# countdown4digit.net
KiCad netlist of a schematic drawn in EAGLE
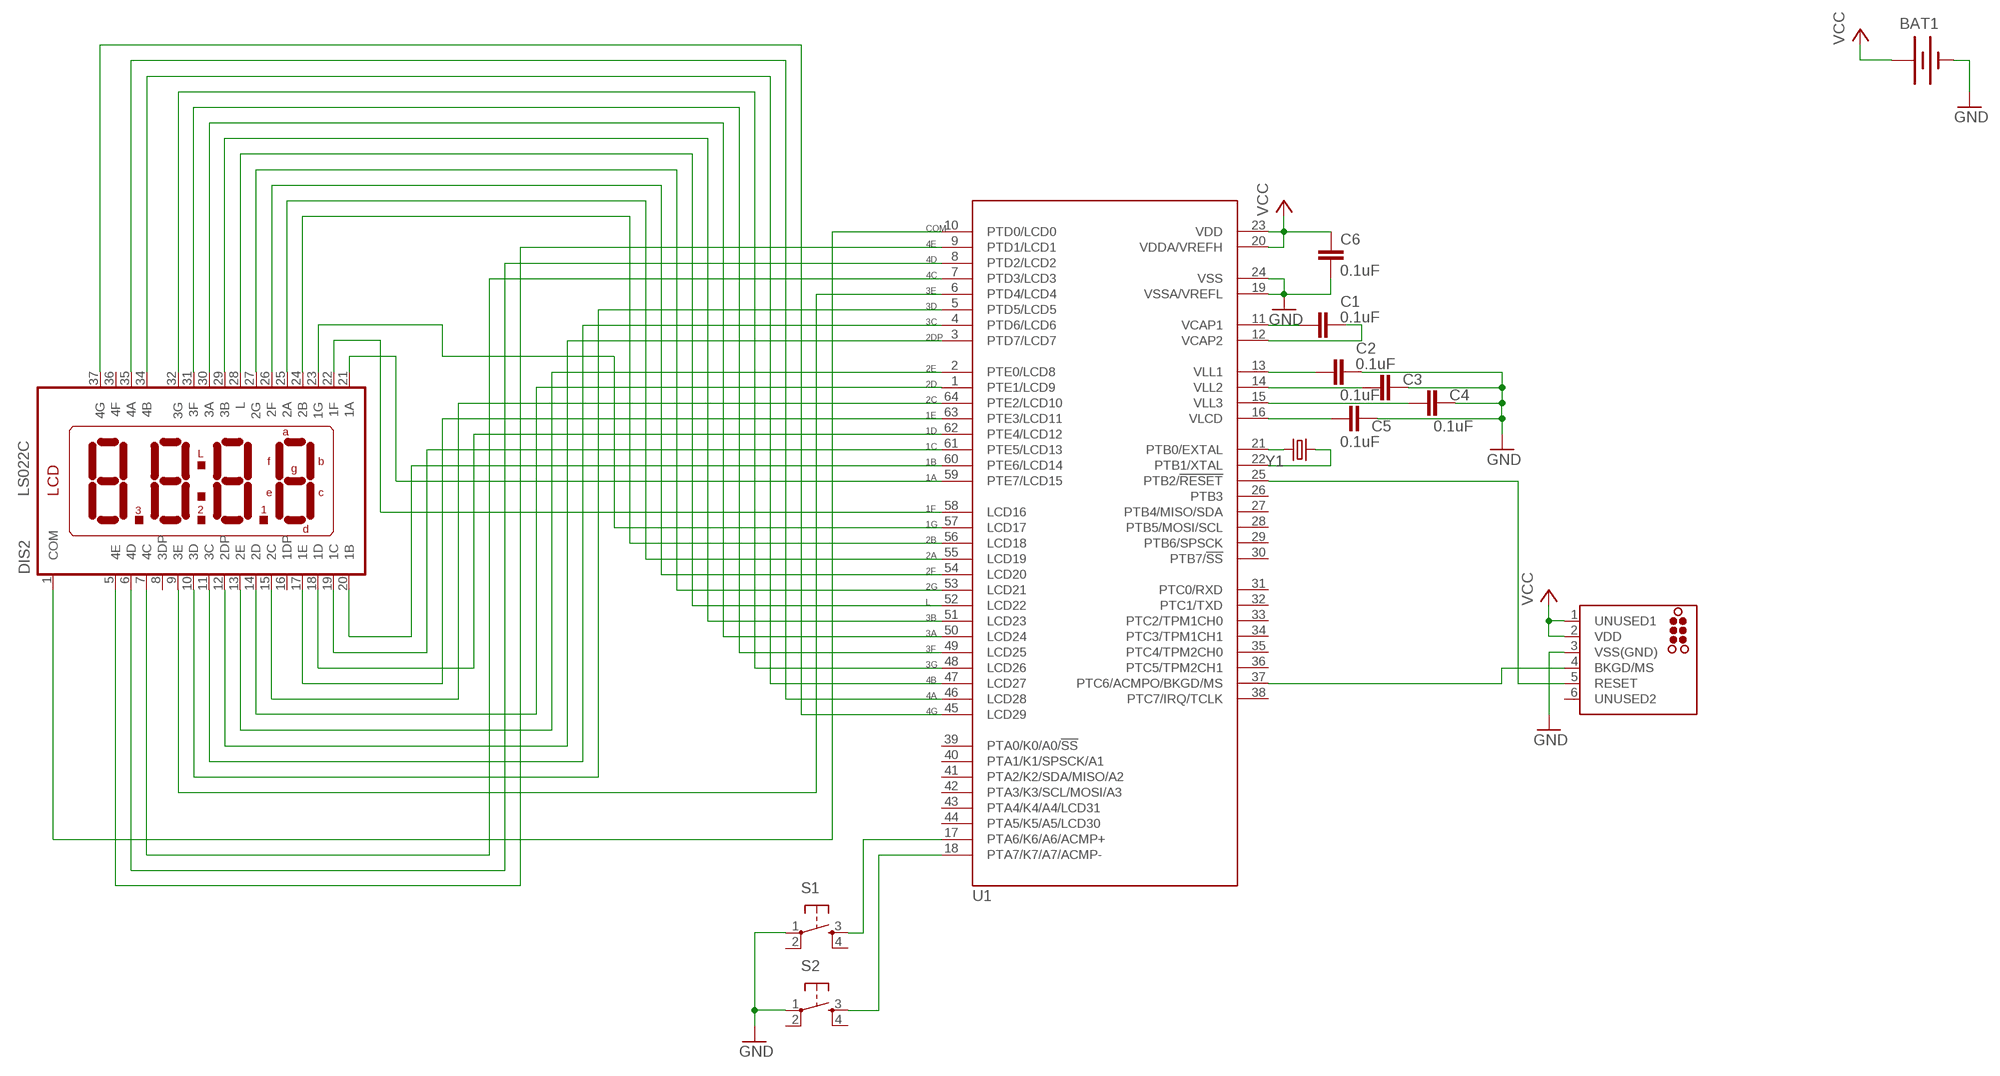
[diagram p0: schematic, sheet 1]

(export (version "E")
  (design (tool "Eeschema 10.0.6"))
  (components
    (comp (ref "BAT1")
      (value "BATTERY12MM")
      (footprint "eagle-import:BATTCON_12MM")
      (libsource (lib "eagle-import") (part "BATTERY12MM"))
    )
    (comp (ref "BDM")
      (value "TC2030-MCP-NL")
      (footprint "eagle-import:TC2030-MCP-NL")
      (libsource (lib "eagle-import") (part "TC2030-MCP-NL"))
    )
    (comp (ref "C1")
      (value "0.1uF")
      (footprint "eagle-import:C0603K")
      (libsource (lib "eagle-import") (part "C-EUC0603K"))
    )
    (comp (ref "C2")
      (value "0.1uF")
      (footprint "eagle-import:C0603K")
      (libsource (lib "eagle-import") (part "C-EUC0603K"))
    )
    (comp (ref "C3")
      (value "0.1uF")
      (footprint "eagle-import:C0603K")
      (libsource (lib "eagle-import") (part "C-EUC0603K"))
    )
    (comp (ref "C4")
      (value "0.1uF")
      (footprint "eagle-import:C0603K")
      (libsource (lib "eagle-import") (part "C-EUC0603K"))
    )
    (comp (ref "C5")
      (value "0.1uF")
      (footprint "eagle-import:C0603K")
      (libsource (lib "eagle-import") (part "C-EUC0603K"))
    )
    (comp (ref "C6")
      (value "0.1uF")
      (footprint "eagle-import:C0603K")
      (libsource (lib "eagle-import") (part "C-EUC0603K"))
    )
    (comp (ref "DIS2")
      (value "LS022C")
      (footprint "eagle-import:LS022C")
      (libsource (lib "eagle-import") (part "LS022C"))
    )
    (comp (ref "S1")
      (value "TAC_SWITCHSMD")
      (footprint "eagle-import:TACTILE_SWITCH_SMD")
      (libsource (lib "eagle-import") (part "TAC_SWITCHSMD"))
    )
    (comp (ref "S2")
      (value "TAC_SWITCHSMD")
      (footprint "eagle-import:TACTILE_SWITCH_SMD")
      (libsource (lib "eagle-import") (part "TAC_SWITCHSMD"))
    )
    (comp (ref "U1")
      (value "MC9S08LL16")
      (footprint "eagle-import:LQFP64")
      (libsource (lib "eagle-import") (part "MC9S08LL16"))
    )
    (comp (ref "Y1")
      (value "CRYSTALTC26H")
      (footprint "eagle-import:TC26H")
      (libsource (lib "eagle-import") (part "CRYSTALTC26H"))
    )
  )
  (nets
    (net (code "1") (name "/1A") (class "Default")
      (node (ref "DIS2") (pin "21") (pinfunction "1A_21") (pintype "passive"))
      (node (ref "U1") (pin "59") (pinfunction "PTE7/LCD15_59") (pintype "bidirectional"))
    )
    (net (code "2") (name "/1B") (class "Default")
      (node (ref "DIS2") (pin "20") (pinfunction "1B_20") (pintype "passive"))
      (node (ref "U1") (pin "60") (pinfunction "PTE6/LCD14_60") (pintype "bidirectional"))
    )
    (net (code "3") (name "/1C") (class "Default")
      (node (ref "DIS2") (pin "19") (pinfunction "1C_19") (pintype "passive"))
      (node (ref "U1") (pin "61") (pinfunction "PTE5/LCD13_61") (pintype "bidirectional"))
    )
    (net (code "4") (name "/1D") (class "Default")
      (node (ref "DIS2") (pin "18") (pinfunction "1D_18") (pintype "passive"))
      (node (ref "U1") (pin "62") (pinfunction "PTE4/LCD12_62") (pintype "bidirectional"))
    )
    (net (code "5") (name "/1E") (class "Default")
      (node (ref "DIS2") (pin "17") (pinfunction "1E_17") (pintype "passive"))
      (node (ref "U1") (pin "63") (pinfunction "PTE3/LCD11_63") (pintype "bidirectional"))
    )
    (net (code "6") (name "/1F") (class "Default")
      (node (ref "DIS2") (pin "22") (pinfunction "1F_22") (pintype "passive"))
      (node (ref "U1") (pin "58") (pinfunction "LCD16_58") (pintype "bidirectional"))
    )
    (net (code "7") (name "/1G") (class "Default")
      (node (ref "DIS2") (pin "23") (pinfunction "1G_23") (pintype "passive"))
      (node (ref "U1") (pin "57") (pinfunction "LCD17_57") (pintype "bidirectional"))
    )
    (net (code "8") (name "/2A") (class "Default")
      (node (ref "DIS2") (pin "25") (pinfunction "2A_25") (pintype "passive"))
      (node (ref "U1") (pin "55") (pinfunction "LCD19_55") (pintype "bidirectional"))
    )
    (net (code "9") (name "/2B") (class "Default")
      (node (ref "DIS2") (pin "24") (pinfunction "2B_24") (pintype "passive"))
      (node (ref "U1") (pin "56") (pinfunction "LCD18_56") (pintype "bidirectional"))
    )
    (net (code "10") (name "/2C") (class "Default")
      (node (ref "DIS2") (pin "15") (pinfunction "2C_15") (pintype "passive"))
      (node (ref "U1") (pin "64") (pinfunction "PTE2/LCD10_64") (pintype "bidirectional"))
    )
    (net (code "11") (name "/2D") (class "Default")
      (node (ref "DIS2") (pin "14") (pinfunction "2D_14") (pintype "passive"))
      (node (ref "U1") (pin "1") (pinfunction "PTE1/LCD9_1") (pintype "bidirectional"))
    )
    (net (code "12") (name "/2DP") (class "Default")
      (node (ref "DIS2") (pin "12") (pinfunction "2DP_12") (pintype "passive"))
      (node (ref "U1") (pin "3") (pinfunction "PTD7/LCD7_3") (pintype "bidirectional"))
    )
    (net (code "13") (name "/2E") (class "Default")
      (node (ref "DIS2") (pin "13") (pinfunction "2E_13") (pintype "passive"))
      (node (ref "U1") (pin "2") (pinfunction "PTE0/LCD8_2") (pintype "bidirectional"))
    )
    (net (code "14") (name "/2F") (class "Default")
      (node (ref "DIS2") (pin "26") (pinfunction "2F_26") (pintype "passive"))
      (node (ref "U1") (pin "54") (pinfunction "LCD20_54") (pintype "bidirectional"))
    )
    (net (code "15") (name "/2G") (class "Default")
      (node (ref "DIS2") (pin "27") (pinfunction "2G_27") (pintype "passive"))
      (node (ref "U1") (pin "53") (pinfunction "LCD21_53") (pintype "bidirectional"))
    )
    (net (code "16") (name "/3A") (class "Default")
      (node (ref "DIS2") (pin "30") (pinfunction "3A_30") (pintype "passive"))
      (node (ref "U1") (pin "50") (pinfunction "LCD24_50") (pintype "bidirectional"))
    )
    (net (code "17") (name "/3B") (class "Default")
      (node (ref "DIS2") (pin "29") (pinfunction "3B_29") (pintype "passive"))
      (node (ref "U1") (pin "51") (pinfunction "LCD23_51") (pintype "bidirectional"))
    )
    (net (code "18") (name "/3C") (class "Default")
      (node (ref "DIS2") (pin "11") (pinfunction "3C_11") (pintype "passive"))
      (node (ref "U1") (pin "4") (pinfunction "PTD6/LCD6_4") (pintype "bidirectional"))
    )
    (net (code "19") (name "/3D") (class "Default")
      (node (ref "DIS2") (pin "10") (pinfunction "3D_10") (pintype "passive"))
      (node (ref "U1") (pin "5") (pinfunction "PTD5/LCD5_5") (pintype "bidirectional"))
    )
    (net (code "20") (name "/3E") (class "Default")
      (node (ref "DIS2") (pin "9") (pinfunction "3E_9") (pintype "passive"))
      (node (ref "U1") (pin "6") (pinfunction "PTD4/LCD4_6") (pintype "bidirectional"))
    )
    (net (code "21") (name "/3F") (class "Default")
      (node (ref "DIS2") (pin "31") (pinfunction "3F_31") (pintype "passive"))
      (node (ref "U1") (pin "49") (pinfunction "LCD25_49") (pintype "bidirectional"))
    )
    (net (code "22") (name "/3G") (class "Default")
      (node (ref "DIS2") (pin "32") (pinfunction "3G_32") (pintype "passive"))
      (node (ref "U1") (pin "48") (pinfunction "LCD26_48") (pintype "bidirectional"))
    )
    (net (code "23") (name "/4A") (class "Default")
      (node (ref "DIS2") (pin "35") (pinfunction "4A_35") (pintype "passive"))
      (node (ref "U1") (pin "46") (pinfunction "LCD28_46") (pintype "bidirectional"))
    )
    (net (code "24") (name "/4B") (class "Default")
      (node (ref "DIS2") (pin "34") (pinfunction "4B_34") (pintype "passive"))
      (node (ref "U1") (pin "47") (pinfunction "LCD27_47") (pintype "bidirectional"))
    )
    (net (code "25") (name "/4C") (class "Default")
      (node (ref "DIS2") (pin "7") (pinfunction "4C_7") (pintype "passive"))
      (node (ref "U1") (pin "7") (pinfunction "PTD3/LCD3_7") (pintype "bidirectional"))
    )
    (net (code "26") (name "/4D") (class "Default")
      (node (ref "DIS2") (pin "6") (pinfunction "4D_6") (pintype "passive"))
      (node (ref "U1") (pin "8") (pinfunction "PTD2/LCD2_8") (pintype "bidirectional"))
    )
    (net (code "27") (name "/4E") (class "Default")
      (node (ref "DIS2") (pin "5") (pinfunction "4E_5") (pintype "passive"))
      (node (ref "U1") (pin "9") (pinfunction "PTD1/LCD1_9") (pintype "bidirectional"))
    )
    (net (code "28") (name "/4G") (class "Default")
      (node (ref "DIS2") (pin "37") (pinfunction "4G_37") (pintype "passive"))
      (node (ref "U1") (pin "45") (pinfunction "LCD29_45") (pintype "bidirectional"))
    )
    (net (code "29") (name "/COM") (class "Default")
      (node (ref "DIS2") (pin "1") (pinfunction "COM_1") (pintype "passive"))
      (node (ref "U1") (pin "10") (pinfunction "PTD0/LCD0_10") (pintype "bidirectional"))
    )
    (net (code "30") (name "/L") (class "Default")
      (node (ref "DIS2") (pin "28") (pinfunction "L_28") (pintype "passive"))
      (node (ref "U1") (pin "52") (pinfunction "LCD22_52") (pintype "bidirectional"))
    )
    (net (code "31") (name "GND") (class "Default")
      (node (ref "BAT1") (pin "GND") (pinfunction "-_GND") (pintype "power_in"))
      (node (ref "BDM") (pin "3") (pinfunction "VSS(GND)_3") (pintype "power_in"))
      (node (ref "C2") (pin "1") (pinfunction "1_1") (pintype "passive"))
      (node (ref "C3") (pin "1") (pinfunction "1_1") (pintype "passive"))
      (node (ref "C4") (pin "1") (pinfunction "1_1") (pintype "passive"))
      (node (ref "C5") (pin "1") (pinfunction "1_1") (pintype "passive"))
      (node (ref "C6") (pin "2") (pinfunction "2_2") (pintype "passive"))
      (node (ref "S1") (pin "1") (pinfunction "1_1") (pintype "passive"))
      (node (ref "S2") (pin "1") (pinfunction "1_1") (pintype "passive"))
      (node (ref "U1") (pin "19") (pinfunction "VSSA/VREFL_19") (pintype "bidirectional"))
      (node (ref "U1") (pin "24") (pinfunction "VSS_24") (pintype "bidirectional"))
    )
    (net (code "32") (name "Net-(BDM-BKGD{slash}MS)") (class "Default")
      (node (ref "BDM") (pin "4") (pinfunction "BKGD/MS_4") (pintype "bidirectional"))
      (node (ref "U1") (pin "37") (pinfunction "PTC6/ACMPO/BKGD/MS_37") (pintype "bidirectional"))
    )
    (net (code "33") (name "Net-(BDM-RESET)") (class "Default")
      (node (ref "BDM") (pin "5") (pinfunction "RESET_5") (pintype "output"))
      (node (ref "U1") (pin "25") (pinfunction "PTB2/~{RESET}_25") (pintype "bidirectional"))
    )
    (net (code "34") (name "Net-(U1-PTA6{slash}K6{slash}A6{slash}ACMP+)") (class "Default")
      (node (ref "S1") (pin "3") (pinfunction "3_3") (pintype "passive"))
      (node (ref "U1") (pin "17") (pinfunction "PTA6/K6/A6/ACMP+_17") (pintype "bidirectional"))
    )
    (net (code "35") (name "Net-(U1-PTA7{slash}K7{slash}A7{slash}ACMP-)") (class "Default")
      (node (ref "S2") (pin "3") (pinfunction "3_3") (pintype "passive"))
      (node (ref "U1") (pin "18") (pinfunction "PTA7/K7/A7/ACMP-_18") (pintype "bidirectional"))
    )
    (net (code "36") (name "Net-(U1-PTB0{slash}EXTAL)") (class "Default")
      (node (ref "U1") (pin "21") (pinfunction "PTB0/EXTAL_21") (pintype "bidirectional"))
      (node (ref "Y1") (pin "2") (pinfunction "2_2") (pintype "passive"))
    )
    (net (code "37") (name "Net-(U1-PTB1{slash}XTAL)") (class "Default")
      (node (ref "U1") (pin "22") (pinfunction "PTB1/XTAL_22") (pintype "bidirectional"))
      (node (ref "Y1") (pin "1") (pinfunction "1_1") (pintype "passive"))
    )
    (net (code "38") (name "Net-(U1-VCAP1)") (class "Default")
      (node (ref "C1") (pin "2") (pinfunction "2_2") (pintype "passive"))
      (node (ref "U1") (pin "11") (pinfunction "VCAP1_11") (pintype "bidirectional"))
    )
    (net (code "39") (name "Net-(U1-VCAP2)") (class "Default")
      (node (ref "C1") (pin "1") (pinfunction "1_1") (pintype "passive"))
      (node (ref "U1") (pin "12") (pinfunction "VCAP2_12") (pintype "bidirectional"))
    )
    (net (code "40") (name "Net-(U1-VLCD)") (class "Default")
      (node (ref "C5") (pin "2") (pinfunction "2_2") (pintype "passive"))
      (node (ref "U1") (pin "16") (pinfunction "VLCD_16") (pintype "bidirectional"))
    )
    (net (code "41") (name "Net-(U1-VLL1)") (class "Default")
      (node (ref "C2") (pin "2") (pinfunction "2_2") (pintype "passive"))
      (node (ref "U1") (pin "13") (pinfunction "VLL1_13") (pintype "bidirectional"))
    )
    (net (code "42") (name "Net-(U1-VLL2)") (class "Default")
      (node (ref "C3") (pin "2") (pinfunction "2_2") (pintype "passive"))
      (node (ref "U1") (pin "14") (pinfunction "VLL2_14") (pintype "bidirectional"))
    )
    (net (code "43") (name "Net-(U1-VLL3)") (class "Default")
      (node (ref "C4") (pin "2") (pinfunction "2_2") (pintype "passive"))
      (node (ref "U1") (pin "15") (pinfunction "VLL3_15") (pintype "bidirectional"))
    )
    (net (code "44") (name "VCC") (class "Default")
      (node (ref "BAT1") (pin "PWR@1") (pinfunction "+_PWR@1") (pintype "power_in"))
      (node (ref "BDM") (pin "1") (pinfunction "UNUSED1_1") (pintype "passive"))
      (node (ref "BDM") (pin "2") (pinfunction "VDD_2") (pintype "power_in"))
      (node (ref "C6") (pin "1") (pinfunction "1_1") (pintype "passive"))
      (node (ref "U1") (pin "20") (pinfunction "VDDA/VREFH_20") (pintype "bidirectional"))
      (node (ref "U1") (pin "23") (pinfunction "VDD_23") (pintype "bidirectional"))
    )
    (net (code "45") (name "unconnected-(BDM-UNUSED2-Pad6)") (class "Default")
      (node (ref "BDM") (pin "6") (pinfunction "UNUSED2_6") (pintype "bidirectional"))
    )
    (net (code "46") (name "unconnected-(DIS2-1DP-Pad16)") (class "Default")
      (node (ref "DIS2") (pin "16") (pinfunction "1DP_16") (pintype "passive"))
    )
    (net (code "47") (name "unconnected-(DIS2-3DP-Pad8)") (class "Default")
      (node (ref "DIS2") (pin "8") (pinfunction "3DP_8") (pintype "passive"))
    )
    (net (code "48") (name "unconnected-(DIS2-4F-Pad36)") (class "Default")
      (node (ref "DIS2") (pin "36") (pinfunction "4F_36") (pintype "passive"))
    )
    (net (code "49") (name "unconnected-(S1-Pad2)") (class "Default")
      (node (ref "S1") (pin "2") (pinfunction "2_2") (pintype "passive"))
    )
    (net (code "50") (name "unconnected-(S1-Pad4)") (class "Default")
      (node (ref "S1") (pin "4") (pinfunction "4_4") (pintype "passive"))
    )
    (net (code "51") (name "unconnected-(S2-Pad2)") (class "Default")
      (node (ref "S2") (pin "2") (pinfunction "2_2") (pintype "passive"))
    )
    (net (code "52") (name "unconnected-(S2-Pad4)") (class "Default")
      (node (ref "S2") (pin "4") (pinfunction "4_4") (pintype "passive"))
    )
    (net (code "53") (name "unconnected-(U1-PTA0{slash}K0{slash}A0{slash}~{SS}-Pad39)") (class "Default")
      (node (ref "U1") (pin "39") (pinfunction "PTA0/K0/A0/~{SS}_39") (pintype "bidirectional"))
    )
    (net (code "54") (name "unconnected-(U1-PTA1{slash}K1{slash}SPSCK{slash}A1-Pad40)") (class "Default")
      (node (ref "U1") (pin "40") (pinfunction "PTA1/K1/SPSCK/A1_40") (pintype "bidirectional"))
    )
    (net (code "55") (name "unconnected-(U1-PTA2{slash}K2{slash}SDA{slash}MISO{slash}A2-Pad41)") (class "Default")
      (node (ref "U1") (pin "41") (pinfunction "PTA2/K2/SDA/MISO/A2_41") (pintype "bidirectional"))
    )
    (net (code "56") (name "unconnected-(U1-PTA3{slash}K3{slash}SCL{slash}MOSI{slash}A3-Pad42)") (class "Default")
      (node (ref "U1") (pin "42") (pinfunction "PTA3/K3/SCL/MOSI/A3_42") (pintype "bidirectional"))
    )
    (net (code "57") (name "unconnected-(U1-PTA4{slash}K4{slash}A4{slash}LCD31-Pad43)") (class "Default")
      (node (ref "U1") (pin "43") (pinfunction "PTA4/K4/A4/LCD31_43") (pintype "bidirectional"))
    )
    (net (code "58") (name "unconnected-(U1-PTA5{slash}K5{slash}A5{slash}LCD30-Pad44)") (class "Default")
      (node (ref "U1") (pin "44") (pinfunction "PTA5/K5/A5/LCD30_44") (pintype "bidirectional"))
    )
    (net (code "59") (name "unconnected-(U1-PTB3-Pad26)") (class "Default")
      (node (ref "U1") (pin "26") (pinfunction "PTB3_26") (pintype "bidirectional"))
    )
    (net (code "60") (name "unconnected-(U1-PTB4{slash}MISO{slash}SDA-Pad27)") (class "Default")
      (node (ref "U1") (pin "27") (pinfunction "PTB4/MISO/SDA_27") (pintype "bidirectional"))
    )
    (net (code "61") (name "unconnected-(U1-PTB5{slash}MOSI{slash}SCL-Pad28)") (class "Default")
      (node (ref "U1") (pin "28") (pinfunction "PTB5/MOSI/SCL_28") (pintype "bidirectional"))
    )
    (net (code "62") (name "unconnected-(U1-PTB6{slash}SPSCK-Pad29)") (class "Default")
      (node (ref "U1") (pin "29") (pinfunction "PTB6/SPSCK_29") (pintype "bidirectional"))
    )
    (net (code "63") (name "unconnected-(U1-PTB7{slash}~{SS}-Pad30)") (class "Default")
      (node (ref "U1") (pin "30") (pinfunction "PTB7/~{SS}_30") (pintype "bidirectional"))
    )
    (net (code "64") (name "unconnected-(U1-PTC0{slash}RXD-Pad31)") (class "Default")
      (node (ref "U1") (pin "31") (pinfunction "PTC0/RXD_31") (pintype "bidirectional"))
    )
    (net (code "65") (name "unconnected-(U1-PTC1{slash}TXD-Pad32)") (class "Default")
      (node (ref "U1") (pin "32") (pinfunction "PTC1/TXD_32") (pintype "bidirectional"))
    )
    (net (code "66") (name "unconnected-(U1-PTC2{slash}TPM1CH0-Pad33)") (class "Default")
      (node (ref "U1") (pin "33") (pinfunction "PTC2/TPM1CH0_33") (pintype "bidirectional"))
    )
    (net (code "67") (name "unconnected-(U1-PTC3{slash}TPM1CH1-Pad34)") (class "Default")
      (node (ref "U1") (pin "34") (pinfunction "PTC3/TPM1CH1_34") (pintype "bidirectional"))
    )
    (net (code "68") (name "unconnected-(U1-PTC4{slash}TPM2CH0-Pad35)") (class "Default")
      (node (ref "U1") (pin "35") (pinfunction "PTC4/TPM2CH0_35") (pintype "bidirectional"))
    )
    (net (code "69") (name "unconnected-(U1-PTC5{slash}TPM2CH1-Pad36)") (class "Default")
      (node (ref "U1") (pin "36") (pinfunction "PTC5/TPM2CH1_36") (pintype "bidirectional"))
    )
    (net (code "70") (name "unconnected-(U1-PTC7{slash}IRQ{slash}TCLK-Pad38)") (class "Default")
      (node (ref "U1") (pin "38") (pinfunction "PTC7/IRQ/TCLK_38") (pintype "bidirectional"))
    )
  )
)
